# p20-001.net
KiCad netlist of a schematic drawn in EAGLE
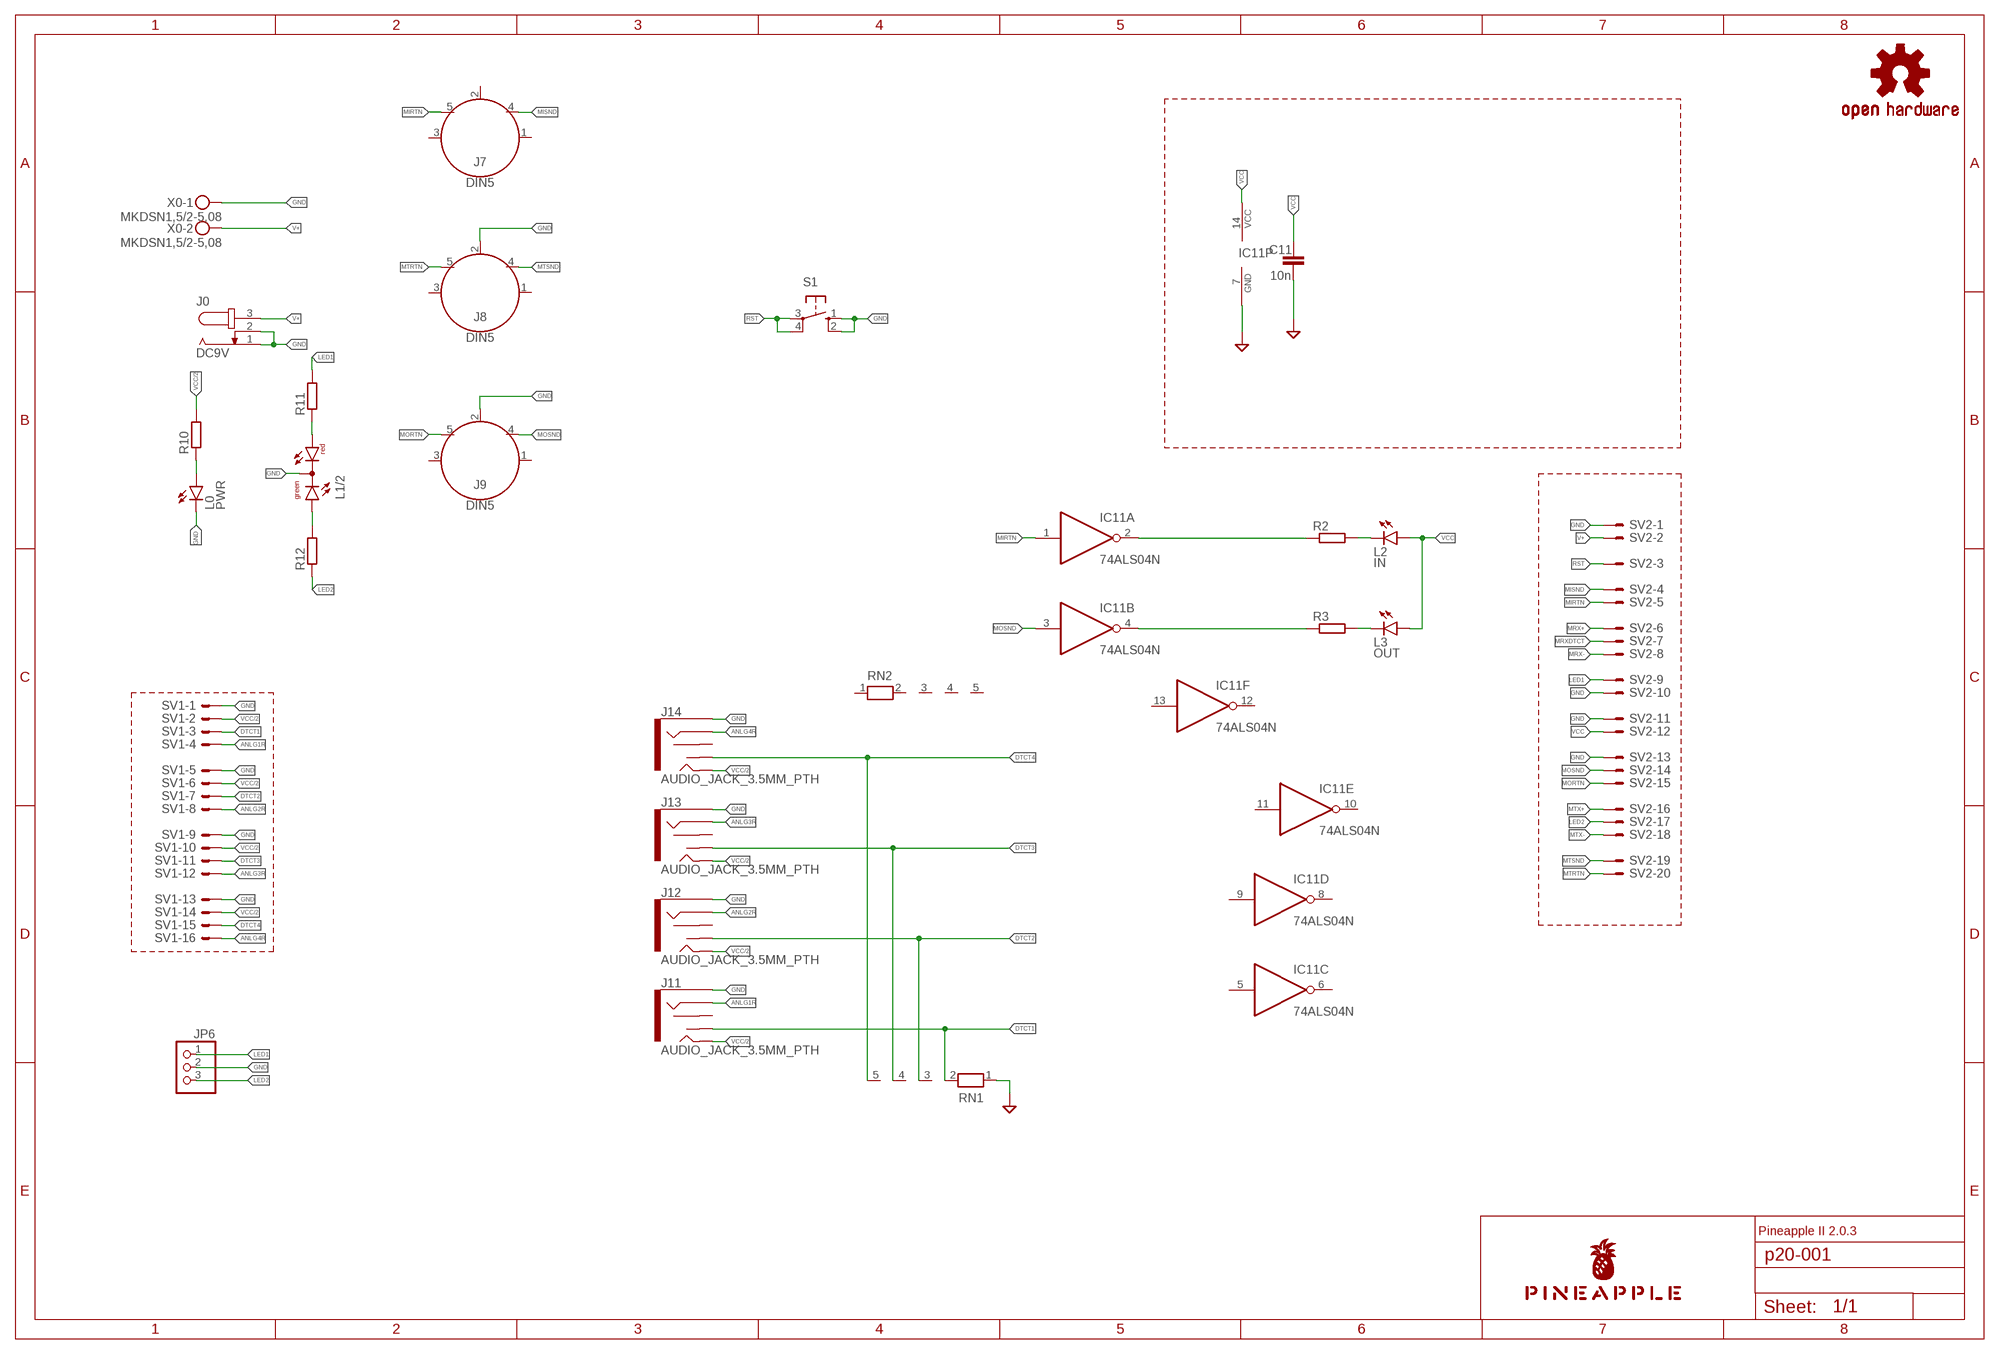
[diagram p0: schematic, sheet 1]

(export (version "E")
  (design (tool "Eeschema 10.0.6"))
  (components
    (comp (ref "C11")
      (value "10n")
      (footprint "eagle-import:C025-024X044")
      (libsource (lib "eagle-import") (part "C-EU025-024X044"))
    )
    (comp (ref "IC11")
      (value "74ALS04N")
      (footprint "eagle-import:DIL14")
      (libsource (lib "eagle-import") (part "7404NALS"))
    )
    (comp (ref "J0")
      (value "DC9V")
      (footprint "eagle-import:SPC4077")
      (libsource (lib "eagle-import") (part "JACK-PLUG0"))
    )
    (comp (ref "J7")
      (value "DIN5")
      (footprint "eagle-import:DIN5-RA-PTH")
      (libsource (lib "eagle-import") (part "DIN5"))
    )
    (comp (ref "J8")
      (value "DIN5")
      (footprint "eagle-import:DIN5-RA-PTH")
      (libsource (lib "eagle-import") (part "DIN5"))
    )
    (comp (ref "J9")
      (value "DIN5")
      (footprint "eagle-import:DIN5-RA-PTH")
      (libsource (lib "eagle-import") (part "DIN5"))
    )
    (comp (ref "J11")
      (value "AUDIO_JACK_3.5MM_PTH")
      (footprint "eagle-import:AUDIO-JACK")
      (libsource (lib "eagle-import") (part "AUDIO_JACK_3.5MM_PTH"))
    )
    (comp (ref "J12")
      (value "AUDIO_JACK_3.5MM_PTH")
      (footprint "eagle-import:AUDIO-JACK")
      (libsource (lib "eagle-import") (part "AUDIO_JACK_3.5MM_PTH"))
    )
    (comp (ref "J13")
      (value "AUDIO_JACK_3.5MM_PTH")
      (footprint "eagle-import:AUDIO-JACK")
      (libsource (lib "eagle-import") (part "AUDIO_JACK_3.5MM_PTH"))
    )
    (comp (ref "J14")
      (value "AUDIO_JACK_3.5MM_PTH")
      (footprint "eagle-import:AUDIO-JACK")
      (libsource (lib "eagle-import") (part "AUDIO_JACK_3.5MM_PTH"))
    )
    (comp (ref "JP6")
      (value "PINHD-1X3")
      (footprint "eagle-import:1X03")
      (libsource (lib "eagle-import") (part "PINHD-1X3"))
    )
    (comp (ref "L0")
      (value "PWR")
      (footprint "eagle-import:LED3MM")
      (libsource (lib "eagle-import") (part "LED3MM"))
    )
    (comp (ref "L1/2")
      (value "DUOLED-RG-C")
      (footprint "eagle-import:DUOLED-C-5MM")
      (libsource (lib "eagle-import") (part "DUOLED-RG-C"))
    )
    (comp (ref "L2")
      (value "IN")
      (footprint "eagle-import:LED3MM")
      (libsource (lib "eagle-import") (part "LED3MM"))
    )
    (comp (ref "L3")
      (value "OUT")
      (footprint "eagle-import:LED3MM")
      (libsource (lib "eagle-import") (part "LED3MM"))
    )
    (comp (ref "LOGO1")
      (value "OSHW-LOGOS-COPPER")
      (footprint "eagle-import:OSHW-LOGO-S_COPPER")
      (libsource (lib "eagle-import") (part "OSHW-LOGOS-COPPER"))
    )
    (comp (ref "R2")
      (value "R-EU_0204/5")
      (footprint "eagle-import:0204_5")
      (libsource (lib "eagle-import") (part "R-EU_0204/5"))
    )
    (comp (ref "R3")
      (value "R-EU_0204/5")
      (footprint "eagle-import:0204_5")
      (libsource (lib "eagle-import") (part "R-EU_0204/5"))
    )
    (comp (ref "R10")
      (value "R-EU_0204/5")
      (footprint "eagle-import:0204_5")
      (libsource (lib "eagle-import") (part "R-EU_0204/5"))
    )
    (comp (ref "R11")
      (value "R-EU_0204/5")
      (footprint "eagle-import:0204_5")
      (libsource (lib "eagle-import") (part "R-EU_0204/5"))
    )
    (comp (ref "R12")
      (value "R-EU_0204/5")
      (footprint "eagle-import:0204_5")
      (libsource (lib "eagle-import") (part "R-EU_0204/5"))
    )
    (comp (ref "RN1")
      (value "RN04")
      (footprint "eagle-import:RN-5")
      (libsource (lib "eagle-import") (part "RN04"))
    )
    (comp (ref "RN2")
      (value "RN04")
      (footprint "eagle-import:RN-5")
      (libsource (lib "eagle-import") (part "RN04"))
    )
    (comp (ref "S1")
      (value "10-XX")
      (footprint "eagle-import:B3F-10XX")
      (fields (field (name "MPN") "B3F-1000"))
      (libsource (lib "eagle-import") (part "10-XX"))
    )
    (comp (ref "SV1")
      (value "ML16LE")
      (footprint "eagle-import:ML16L")
      (libsource (lib "eagle-import") (part "ML16LE"))
    )
    (comp (ref "SV2")
      (value "ML20LE")
      (footprint "eagle-import:ML20L")
      (libsource (lib "eagle-import") (part "ML20LE"))
    )
    (comp (ref "U$1")
      (value "PINEAPPLE450_SILK")
      (footprint "eagle-import:PINEAPPLE450_SILK")
      (libsource (lib "eagle-import") (part "PINEAPPLE450_SILK"))
    )
    (comp (ref "X0")
      (value "MKDSN1,5/2-5,08")
      (footprint "eagle-import:MKDSN1,5_2-5,08")
      (libsource (lib "eagle-import") (part "MKDSN1,5/2-5,08"))
    )
  )
  (nets
    (net (code "1") (name "ANLG1R") (class "Default")
      (node (ref "J11") (pin "RING") (pinfunction "RING_RING") (pintype "bidirectional"))
      (node (ref "SV1") (pin "4") (pinfunction "S_4") (pintype "passive"))
    )
    (net (code "2") (name "ANLG2R") (class "Default")
      (node (ref "J12") (pin "RING") (pinfunction "RING_RING") (pintype "bidirectional"))
      (node (ref "SV1") (pin "8") (pinfunction "S_8") (pintype "passive"))
    )
    (net (code "3") (name "ANLG3R") (class "Default")
      (node (ref "J13") (pin "RING") (pinfunction "RING_RING") (pintype "bidirectional"))
      (node (ref "SV1") (pin "12") (pinfunction "S_12") (pintype "passive"))
    )
    (net (code "4") (name "ANLG4R") (class "Default")
      (node (ref "J14") (pin "RING") (pinfunction "RING_RING") (pintype "bidirectional"))
      (node (ref "SV1") (pin "16") (pinfunction "S_16") (pintype "passive"))
    )
    (net (code "5") (name "DTCT1") (class "Default")
      (node (ref "J11") (pin "TSH") (pinfunction "TSH_TSH") (pintype "bidirectional"))
      (node (ref "RN1") (pin "2") (pinfunction "2_2") (pintype "passive"))
      (node (ref "SV1") (pin "3") (pinfunction "S_3") (pintype "passive"))
    )
    (net (code "6") (name "DTCT2") (class "Default")
      (node (ref "J12") (pin "TSH") (pinfunction "TSH_TSH") (pintype "bidirectional"))
      (node (ref "RN1") (pin "3") (pinfunction "3_3") (pintype "passive"))
      (node (ref "SV1") (pin "7") (pinfunction "S_7") (pintype "passive"))
    )
    (net (code "7") (name "DTCT3") (class "Default")
      (node (ref "J13") (pin "TSH") (pinfunction "TSH_TSH") (pintype "bidirectional"))
      (node (ref "RN1") (pin "4") (pinfunction "4_4") (pintype "passive"))
      (node (ref "SV1") (pin "11") (pinfunction "S_11") (pintype "passive"))
    )
    (net (code "8") (name "DTCT4") (class "Default")
      (node (ref "J14") (pin "TSH") (pinfunction "TSH_TSH") (pintype "bidirectional"))
      (node (ref "RN1") (pin "5") (pinfunction "5_5") (pintype "passive"))
      (node (ref "SV1") (pin "15") (pinfunction "S_15") (pintype "passive"))
    )
    (net (code "9") (name "GND") (class "Default")
      (node (ref "C11") (pin "2") (pinfunction "2_2") (pintype "passive"))
      (node (ref "IC11") (pin "7") (pinfunction "GND_7") (pintype "power_in"))
      (node (ref "J0") (pin "1") (pinfunction "1_1") (pintype "passive"))
      (node (ref "J0") (pin "2") (pinfunction "2_2") (pintype "passive"))
      (node (ref "J11") (pin "SLEEVE") (pinfunction "SLEEVE_SLEEVE") (pintype "bidirectional"))
      (node (ref "J12") (pin "SLEEVE") (pinfunction "SLEEVE_SLEEVE") (pintype "bidirectional"))
      (node (ref "J13") (pin "SLEEVE") (pinfunction "SLEEVE_SLEEVE") (pintype "bidirectional"))
      (node (ref "J14") (pin "SLEEVE") (pinfunction "SLEEVE_SLEEVE") (pintype "bidirectional"))
      (node (ref "J8") (pin "2") (pinfunction "2_2") (pintype "bidirectional"))
      (node (ref "J9") (pin "2") (pinfunction "2_2") (pintype "bidirectional"))
      (node (ref "JP6") (pin "2") (pinfunction "2_2") (pintype "passive"))
      (node (ref "L0") (pin "K") (pinfunction "C_K") (pintype "passive"))
      (node (ref "L1/2") (pin "C") (pinfunction "C_C") (pintype "passive"))
      (node (ref "RN1") (pin "1") (pinfunction "1_1") (pintype "passive"))
      (node (ref "S1") (pin "1") (pinfunction "S_1") (pintype "passive"))
      (node (ref "S1") (pin "2") (pinfunction "S1_2") (pintype "passive"))
      (node (ref "SV1") (pin "1") (pinfunction "S_1") (pintype "passive"))
      (node (ref "SV1") (pin "13") (pinfunction "S_13") (pintype "passive"))
      (node (ref "SV1") (pin "5") (pinfunction "S_5") (pintype "passive"))
      (node (ref "SV1") (pin "9") (pinfunction "S_9") (pintype "passive"))
      (node (ref "SV2") (pin "1") (pinfunction "S_1") (pintype "passive"))
      (node (ref "SV2") (pin "10") (pinfunction "S_10") (pintype "passive"))
      (node (ref "SV2") (pin "11") (pinfunction "S_11") (pintype "passive"))
      (node (ref "SV2") (pin "13") (pinfunction "S_13") (pintype "passive"))
      (node (ref "X0") (pin "1") (pinfunction "KL_1") (pintype "passive"))
    )
    (net (code "10") (name "LED1") (class "Default")
      (node (ref "JP6") (pin "1") (pinfunction "1_1") (pintype "passive"))
      (node (ref "R11") (pin "2") (pinfunction "2_2") (pintype "passive"))
      (node (ref "SV2") (pin "9") (pinfunction "S_9") (pintype "passive"))
    )
    (net (code "11") (name "LED2") (class "Default")
      (node (ref "JP6") (pin "3") (pinfunction "3_3") (pintype "passive"))
      (node (ref "R12") (pin "1") (pinfunction "1_1") (pintype "passive"))
      (node (ref "SV2") (pin "17") (pinfunction "S_17") (pintype "passive"))
    )
    (net (code "12") (name "MIRTN") (class "Default")
      (node (ref "IC11") (pin "1") (pinfunction "I_1") (pintype "input"))
      (node (ref "J7") (pin "5") (pinfunction "5_5") (pintype "bidirectional"))
      (node (ref "SV2") (pin "5") (pinfunction "S_5") (pintype "passive"))
    )
    (net (code "13") (name "MISND") (class "Default")
      (node (ref "J7") (pin "4") (pinfunction "4_4") (pintype "bidirectional"))
      (node (ref "SV2") (pin "4") (pinfunction "S_4") (pintype "passive"))
    )
    (net (code "14") (name "MORTN") (class "Default")
      (node (ref "J9") (pin "5") (pinfunction "5_5") (pintype "bidirectional"))
      (node (ref "SV2") (pin "15") (pinfunction "S_15") (pintype "passive"))
    )
    (net (code "15") (name "MOSND") (class "Default")
      (node (ref "IC11") (pin "3") (pinfunction "I_3") (pintype "input"))
      (node (ref "J9") (pin "4") (pinfunction "4_4") (pintype "bidirectional"))
      (node (ref "SV2") (pin "14") (pinfunction "S_14") (pintype "passive"))
    )
    (net (code "16") (name "MRX+") (class "Default")
      (node (ref "SV2") (pin "6") (pinfunction "S_6") (pintype "passive"))
    )
    (net (code "17") (name "MRX-") (class "Default")
      (node (ref "SV2") (pin "8") (pinfunction "S_8") (pintype "passive"))
    )
    (net (code "18") (name "MRXDTCT") (class "Default")
      (node (ref "SV2") (pin "7") (pinfunction "S_7") (pintype "passive"))
    )
    (net (code "19") (name "MTRTN") (class "Default")
      (node (ref "J8") (pin "5") (pinfunction "5_5") (pintype "bidirectional"))
      (node (ref "SV2") (pin "20") (pinfunction "S_20") (pintype "passive"))
    )
    (net (code "20") (name "MTSND") (class "Default")
      (node (ref "J8") (pin "4") (pinfunction "4_4") (pintype "bidirectional"))
      (node (ref "SV2") (pin "19") (pinfunction "S_19") (pintype "passive"))
    )
    (net (code "21") (name "MTX+") (class "Default")
      (node (ref "SV2") (pin "16") (pinfunction "S_16") (pintype "passive"))
    )
    (net (code "22") (name "MTX-") (class "Default")
      (node (ref "SV2") (pin "18") (pinfunction "S_18") (pintype "passive"))
    )
    (net (code "23") (name "Net-(IC11A-O)") (class "Default")
      (node (ref "IC11") (pin "2") (pinfunction "O_2") (pintype "output"))
      (node (ref "R2") (pin "1") (pinfunction "1_1") (pintype "passive"))
    )
    (net (code "24") (name "Net-(IC11B-O)") (class "Default")
      (node (ref "IC11") (pin "4") (pinfunction "O_4") (pintype "output"))
      (node (ref "R3") (pin "1") (pinfunction "1_1") (pintype "passive"))
    )
    (net (code "25") (name "Net-(L0-PadA)") (class "Default")
      (node (ref "L0") (pin "A") (pinfunction "A_A") (pintype "passive"))
      (node (ref "R10") (pin "1") (pinfunction "1_1") (pintype "passive"))
    )
    (net (code "26") (name "Net-(L1/2-AG)") (class "Default")
      (node (ref "L1/2") (pin "AX") (pinfunction "AG_AX") (pintype "passive"))
      (node (ref "R12") (pin "2") (pinfunction "2_2") (pintype "passive"))
    )
    (net (code "27") (name "Net-(L1/2-PadAR)") (class "Default")
      (node (ref "L1/2") (pin "AR") (pinfunction "AR_AR") (pintype "passive"))
      (node (ref "R11") (pin "1") (pinfunction "1_1") (pintype "passive"))
    )
    (net (code "28") (name "Net-(L2-C)") (class "Default")
      (node (ref "L2") (pin "K") (pinfunction "C_K") (pintype "passive"))
      (node (ref "R2") (pin "2") (pinfunction "2_2") (pintype "passive"))
    )
    (net (code "29") (name "Net-(L3-C)") (class "Default")
      (node (ref "L3") (pin "K") (pinfunction "C_K") (pintype "passive"))
      (node (ref "R3") (pin "2") (pinfunction "2_2") (pintype "passive"))
    )
    (net (code "30") (name "RST") (class "Default")
      (node (ref "S1") (pin "3") (pinfunction "P_3") (pintype "passive"))
      (node (ref "S1") (pin "4") (pinfunction "P1_4") (pintype "passive"))
      (node (ref "SV2") (pin "3") (pinfunction "S_3") (pintype "passive"))
    )
    (net (code "31") (name "V+") (class "Default")
      (node (ref "J0") (pin "3") (pinfunction "3_3") (pintype "passive"))
      (node (ref "SV2") (pin "2") (pinfunction "S_2") (pintype "passive"))
      (node (ref "X0") (pin "2") (pinfunction "KL_2") (pintype "passive"))
    )
    (net (code "32") (name "VCC") (class "Default")
      (node (ref "C11") (pin "1") (pinfunction "1_1") (pintype "passive"))
      (node (ref "IC11") (pin "14") (pinfunction "VCC_14") (pintype "power_in"))
      (node (ref "L2") (pin "A") (pinfunction "A_A") (pintype "passive"))
      (node (ref "L3") (pin "A") (pinfunction "A_A") (pintype "passive"))
      (node (ref "SV2") (pin "12") (pinfunction "S_12") (pintype "passive"))
    )
    (net (code "33") (name "VCC{slash}2") (class "Default")
      (node (ref "J11") (pin "TIP") (pinfunction "TIP_TIP") (pintype "bidirectional"))
      (node (ref "J12") (pin "TIP") (pinfunction "TIP_TIP") (pintype "bidirectional"))
      (node (ref "J13") (pin "TIP") (pinfunction "TIP_TIP") (pintype "bidirectional"))
      (node (ref "J14") (pin "TIP") (pinfunction "TIP_TIP") (pintype "bidirectional"))
      (node (ref "R10") (pin "2") (pinfunction "2_2") (pintype "passive"))
      (node (ref "SV1") (pin "10") (pinfunction "S_10") (pintype "passive"))
      (node (ref "SV1") (pin "14") (pinfunction "S_14") (pintype "passive"))
      (node (ref "SV1") (pin "2") (pinfunction "S_2") (pintype "passive"))
      (node (ref "SV1") (pin "6") (pinfunction "S_6") (pintype "passive"))
    )
    (net (code "34") (name "unconnected-(IC11C-I-Pad5)") (class "Default")
      (node (ref "IC11") (pin "5") (pinfunction "I_5") (pintype "input"))
    )
    (net (code "35") (name "unconnected-(IC11C-O-Pad6)") (class "Default")
      (node (ref "IC11") (pin "6") (pinfunction "O_6") (pintype "output"))
    )
    (net (code "36") (name "unconnected-(IC11D-I-Pad9)") (class "Default")
      (node (ref "IC11") (pin "9") (pinfunction "I_9") (pintype "input"))
    )
    (net (code "37") (name "unconnected-(IC11D-O-Pad8)") (class "Default")
      (node (ref "IC11") (pin "8") (pinfunction "O_8") (pintype "output"))
    )
    (net (code "38") (name "unconnected-(IC11E-I-Pad11)") (class "Default")
      (node (ref "IC11") (pin "11") (pinfunction "I_11") (pintype "input"))
    )
    (net (code "39") (name "unconnected-(IC11E-O-Pad10)") (class "Default")
      (node (ref "IC11") (pin "10") (pinfunction "O_10") (pintype "output"))
    )
    (net (code "40") (name "unconnected-(IC11F-I-Pad13)") (class "Default")
      (node (ref "IC11") (pin "13") (pinfunction "I_13") (pintype "input"))
    )
    (net (code "41") (name "unconnected-(IC11F-O-Pad12)") (class "Default")
      (node (ref "IC11") (pin "12") (pinfunction "O_12") (pintype "output"))
    )
    (net (code "42") (name "unconnected-(J7-Pad1)") (class "Default")
      (node (ref "J7") (pin "1") (pinfunction "1_1") (pintype "bidirectional"))
    )
    (net (code "43") (name "unconnected-(J7-Pad2)") (class "Default")
      (node (ref "J7") (pin "2") (pinfunction "2_2") (pintype "bidirectional"))
    )
    (net (code "44") (name "unconnected-(J7-Pad3)") (class "Default")
      (node (ref "J7") (pin "3") (pinfunction "3_3") (pintype "bidirectional"))
    )
    (net (code "45") (name "unconnected-(J8-Pad1)") (class "Default")
      (node (ref "J8") (pin "1") (pinfunction "1_1") (pintype "bidirectional"))
    )
    (net (code "46") (name "unconnected-(J8-Pad3)") (class "Default")
      (node (ref "J8") (pin "3") (pinfunction "3_3") (pintype "bidirectional"))
    )
    (net (code "47") (name "unconnected-(J9-Pad1)") (class "Default")
      (node (ref "J9") (pin "1") (pinfunction "1_1") (pintype "bidirectional"))
    )
    (net (code "48") (name "unconnected-(J9-Pad3)") (class "Default")
      (node (ref "J9") (pin "3") (pinfunction "3_3") (pintype "bidirectional"))
    )
    (net (code "49") (name "unconnected-(J11-PadRSH)") (class "Default")
      (node (ref "J11") (pin "RSH") (pinfunction "RSH_RSH") (pintype "bidirectional"))
    )
    (net (code "50") (name "unconnected-(J12-PadRSH)") (class "Default")
      (node (ref "J12") (pin "RSH") (pinfunction "RSH_RSH") (pintype "bidirectional"))
    )
    (net (code "51") (name "unconnected-(J13-PadRSH)") (class "Default")
      (node (ref "J13") (pin "RSH") (pinfunction "RSH_RSH") (pintype "bidirectional"))
    )
    (net (code "52") (name "unconnected-(J14-PadRSH)") (class "Default")
      (node (ref "J14") (pin "RSH") (pinfunction "RSH_RSH") (pintype "bidirectional"))
    )
    (net (code "53") (name "unconnected-(RN2-Pad1)") (class "Default")
      (node (ref "RN2") (pin "1") (pinfunction "1_1") (pintype "passive"))
    )
    (net (code "54") (name "unconnected-(RN2-Pad2)") (class "Default")
      (node (ref "RN2") (pin "2") (pinfunction "2_2") (pintype "passive"))
    )
    (net (code "55") (name "unconnected-(RN2-Pad3)") (class "Default")
      (node (ref "RN2") (pin "3") (pinfunction "3_3") (pintype "passive"))
    )
    (net (code "56") (name "unconnected-(RN2-Pad4)") (class "Default")
      (node (ref "RN2") (pin "4") (pinfunction "4_4") (pintype "passive"))
    )
    (net (code "57") (name "unconnected-(RN2-Pad5)") (class "Default")
      (node (ref "RN2") (pin "5") (pinfunction "5_5") (pintype "passive"))
    )
  )
)
